# Boost_converter.net
KiCad netlist of a schematic drawn in Altium Designer
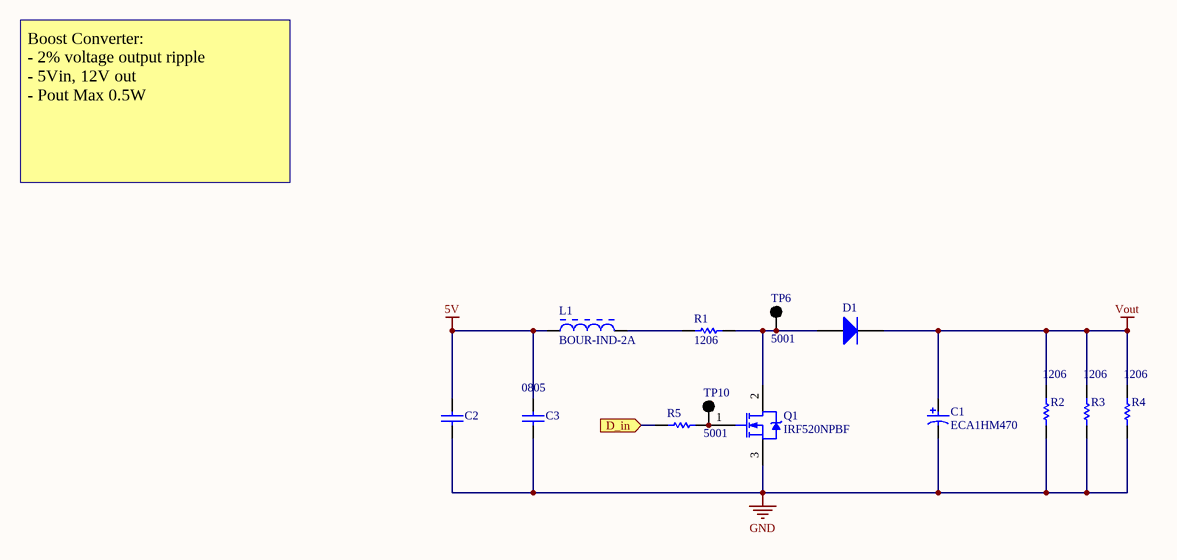
[diagram p0: Boost_converter.SchDoc]

(export (version "E")
  (design (tool "Eeschema 10.0.6"))
  (components
    (comp (ref "C1")
      (value "ECA1HM470")
      (footprint "CAPPR55-250-1120X630X1220")
      (description "Aluminum Electrolytic Capacitor, 47 uF, +/- 20%, 50 V, -40 to 85 degC, 2-Pin THD, RoHS, Bulk")
      (fields (field (name "MANUFACTURER") "Panasonic") (field (name "TOLERANCE") "20%"))
      (libsource (lib "Altium Content Vault") (part "CMP-2100-03626-1"))
    )
    (comp (ref "C2")
      (value "CAP 0.5pF 50V 0805(2012)")
      (footprint "CAPC0805(2012)75_M")
      (description "CAP 0.5pF 50V ±0.1pF 0805 (2012 Metric) Thickness 0.75mm SMD")
      (fields (field (name "TOLERANCE") "Â±0.1pF"))
      (libsource (lib "Altium Content Vault") (part "CMP-1036-00018-1"))
    )
    (comp (ref "C3")
      (value "CAP 0.5pF 50V 0805(2012)")
      (footprint "CAPC0805(2012)75_M")
      (description "CAP 0.5pF 50V ±0.1pF 0805 (2012 Metric) Thickness 0.75mm SMD")
      (fields (field (name "CASE-EIA") "0805") (field (name "TOLERANCE") "Â±0.1pF"))
      (libsource (lib "Altium Content Vault") (part "CMP-1036-00018-1"))
    )
    (comp (ref "D1")
      (value "~")
      (footprint "DIOD-S1M-13-F-SMA-2_V")
      (fields (field (name "MANUFACTURER") "Diodes Inc") (field (name "PARTNUMBER") "S1M-13-F"))
      (libsource (lib "Altium Content Vault") (part "DIOD-D-A1K2-2"))
    )
    (comp (ref "L1")
      (value "BOUR-IND-2A")
      (footprint "SRR1208 Inductor")
      (libsource (lib "Boost_lib") (part "BOUR-IND-2A"))
    )
    (comp (ref "Q1")
      (value "IRF520NPBF")
      (footprint "INTR-TO-220AB-3")
      (description "HEXFET(R) Power MOSFET, 100 V, 9.7 A, 0.2 Ohm, -55 to 175 degC, 3-Pin FM (TO-220AB), RoHS, Tube")
      (fields (field (name "MANUFACTURER") "International Rectifier"))
      (libsource (lib "Altium Content Vault") (part "NEMOS-GDS-3_B"))
    )
    (comp (ref "R1")
      (value "1K43 1% 1206(3216)")
      (footprint "RESC1206(3216)_M")
      (description "1K43 0.25W 1% 1206 (3216 Metric)  SMD")
      (fields
        (field (name "POWER") "0.25 W")
        (field (name "CASE-EIA") "1206")
        (field (name "TOLERANCE") "1 %")
      )
      (libsource (lib "Altium Content Vault") (part "CMP-1014-00526-1"))
    )
    (comp (ref "R2")
      (value "1K43 1% 1206(3216)")
      (footprint "RESC1206(3216)_M")
      (description "1K43 0.25W 1% 1206 (3216 Metric)  SMD")
      (fields
        (field (name "POWER") "0.25 W")
        (field (name "CASE-EIA") "1206")
        (field (name "TOLERANCE") "1 %")
      )
      (libsource (lib "Altium Content Vault") (part "CMP-1014-00526-1"))
    )
    (comp (ref "R3")
      (value "1K43 1% 1206(3216)")
      (footprint "RESC1206(3216)_M")
      (description "1K43 0.25W 1% 1206 (3216 Metric)  SMD")
      (fields
        (field (name "POWER") "0.25 W")
        (field (name "CASE-EIA") "1206")
        (field (name "TOLERANCE") "1 %")
      )
      (libsource (lib "Altium Content Vault") (part "CMP-1014-00526-1"))
    )
    (comp (ref "R4")
      (value "1K43 1% 1206(3216)")
      (footprint "RESC1206(3216)_M")
      (description "1K43 0.25W 1% 1206 (3216 Metric)  SMD")
      (fields
        (field (name "POWER") "0.25 W")
        (field (name "CASE-EIA") "1206")
        (field (name "TOLERANCE") "1 %")
      )
      (libsource (lib "Altium Content Vault") (part "CMP-1014-00526-1"))
    )
    (comp (ref "R5")
      (value "1K43 1% 1206(3216)")
      (footprint "RESC1206(3216)_M")
      (description "1K43 0.25W 1% 1206 (3216 Metric)  SMD")
      (fields (field (name "POWER") "0.25 W") (field (name "TOLERANCE") "1 %"))
      (libsource (lib "Altium Content Vault") (part "CMP-1014-00526-1"))
    )
    (comp (ref "TP6")
      (value "5001")
      (footprint "KSTN-5001")
      (description "Test Point, Black, 1-Pin THD, RoHS, Bulk")
      (fields (field (name "MANUFACTURER") "Keystone"))
      (libsource (lib "Altium Content Vault") (part "KSTN-TP-5001"))
    )
    (comp (ref "TP10")
      (value "5001")
      (footprint "KSTN-5001")
      (description "Test Point, Black, 1-Pin THD, RoHS, Bulk")
      (fields (field (name "MANUFACTURER") "Keystone"))
      (libsource (lib "Altium Content Vault") (part "KSTN-TP-5001"))
    )
  )
  (nets
    (net (code "1") (name "/D_in") (class "Default")
      (node (ref "R5") (pin "2") (pinfunction "2_2") (pintype "passive"))
    )
    (net (code "2") (name "5V") (class "Default")
      (node (ref "C2") (pin "2") (pinfunction "2_2") (pintype "passive"))
      (node (ref "C3") (pin "2") (pinfunction "2_2") (pintype "passive"))
      (node (ref "L1") (pin "1") (pinfunction "1_1") (pintype "passive"))
    )
    (net (code "3") (name "GND") (class "Default")
      (node (ref "C1") (pin "2") (pinfunction "2_2") (pintype "passive"))
      (node (ref "C2") (pin "1") (pinfunction "1_1") (pintype "passive"))
      (node (ref "C3") (pin "1") (pinfunction "1_1") (pintype "passive"))
      (node (ref "Q1") (pin "3") (pinfunction "S_3") (pintype "passive"))
      (node (ref "R2") (pin "1") (pinfunction "1_1") (pintype "passive"))
      (node (ref "R3") (pin "1") (pinfunction "1_1") (pintype "passive"))
      (node (ref "R4") (pin "1") (pinfunction "1_1") (pintype "passive"))
    )
    (net (code "4") (name "Net-(D1-A)") (class "Default")
      (node (ref "D1") (pin "1") (pinfunction "A_1") (pintype "passive"))
      (node (ref "Q1") (pin "2") (pinfunction "D_2") (pintype "passive"))
      (node (ref "R1") (pin "1") (pinfunction "1_1") (pintype "passive"))
      (node (ref "TP6") (pin "1") (pintype "passive"))
    )
    (net (code "5") (name "Net-(L1-Pad2)") (class "Default")
      (node (ref "L1") (pin "2") (pinfunction "2_2") (pintype "passive"))
      (node (ref "R1") (pin "2") (pinfunction "2_2") (pintype "passive"))
    )
    (net (code "6") (name "Net-(Q1-G)") (class "Default")
      (node (ref "Q1") (pin "1") (pinfunction "G_1") (pintype "passive"))
      (node (ref "R5") (pin "1") (pinfunction "1_1") (pintype "passive"))
      (node (ref "TP10") (pin "1") (pintype "passive"))
    )
    (net (code "7") (name "Vout") (class "Default")
      (node (ref "C1") (pin "1") (pinfunction "1_1") (pintype "passive"))
      (node (ref "D1") (pin "2") (pinfunction "K_2") (pintype "passive"))
      (node (ref "R2") (pin "2") (pinfunction "2_2") (pintype "passive"))
      (node (ref "R3") (pin "2") (pinfunction "2_2") (pintype "passive"))
      (node (ref "R4") (pin "2") (pinfunction "2_2") (pintype "passive"))
    )
  )
)
